# DAC_SPI.net
KiCad netlist of a schematic drawn in Altium Designer
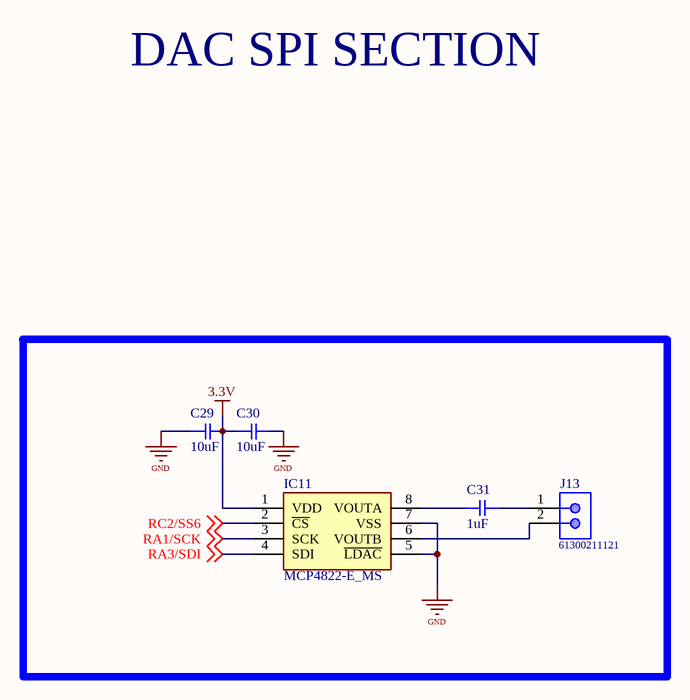
[diagram p0: DAC SPI.SchDoc]

(export (version "E")
  (design (tool "Eeschema 10.0.6"))
  (components
    (comp (ref "C29")
      (value "10uF")
      (footprint "SMD-0805C")
      (description "CAP CER 0.1UF 50V X7R 0805")
      (fields
        (field (name "DIGI-KEY PART NUMBER") "490-11955-1-ND")
        (field (name "PART NUMBER") "GCD21BR71H104KA01L")
      )
      (libsource (lib "capacitor_murata_0805") (part "GCD21BR71H104KA01L"))
    )
    (comp (ref "C30")
      (value "10uF")
      (footprint "SMD-0805C")
      (description "CAP CER 0.1UF 50V X7R 0805")
      (fields
        (field (name "DIGI-KEY PART NUMBER") "490-11955-1-ND")
        (field (name "PART NUMBER") "GCD21BR71H104KA01L")
      )
      (libsource (lib "capacitor_murata_0805") (part "GCD21BR71H104KA01L"))
    )
    (comp (ref "C31")
      (value "1uF")
      (footprint "SMD-0805C")
      (description "CAP CER 0.1UF 50V X7R 0805")
      (fields
        (field (name "DIGI-KEY PART NUMBER") "490-11955-1-ND")
        (field (name "PART NUMBER") "GCD21BR71H104KA01L")
      )
      (libsource (lib "capacitor_murata_0805") (part "GCD21BR71H104KA01L"))
    )
    (comp (ref "IC11")
      (value "MCP4822-E_MS")
      (footprint "SamacSys:SOP65P490X110-8N")
      (description "Integrated Circuit")
      (fields
        (field (name "MANUFACTURER_PART_NUMBER") "MCP4822-E/MS")
        (field (name "MOUSER PART NUMBER") "579-MCP4822-E/MS")
      )
      (libsource (lib "SamacSys") (part "MCP4822-E_MS"))
    )
    (comp (ref "J13")
      (value "61300211121")
      (footprint "61300211121")
      (description "WR-PHD Pin Header, THT, pitch 2.54mm, Single Row, Vertical, 2pin")
      (fields (field (name "PUBLISHER") "Wurth Elektronik"))
      (libsource (lib "SIL_Connectors WR-PHD_rev19a") (part "61300211121"))
    )
  )
  (nets
    (net (code "1") (name "3.3V") (class "Default")
      (node (ref "C29") (pin "2") (pinfunction "2_2") (pintype "passive"))
      (node (ref "C30") (pin "1") (pinfunction "1_1") (pintype "passive"))
      (node (ref "IC11") (pin "1") (pinfunction "VDD_1") (pintype "passive"))
    )
    (net (code "2") (name "GND") (class "Default")
      (node (ref "C29") (pin "1") (pinfunction "1_1") (pintype "passive"))
      (node (ref "C30") (pin "2") (pinfunction "2_2") (pintype "passive"))
      (node (ref "IC11") (pin "5") (pinfunction "~{LDAC}_5") (pintype "passive"))
      (node (ref "IC11") (pin "7") (pinfunction "VSS_7") (pintype "passive"))
    )
    (net (code "3") (name "Net-(C31-Pad1)") (class "Default")
      (node (ref "C31") (pin "1") (pinfunction "1_1") (pintype "passive"))
      (node (ref "J13") (pin "1") (pinfunction "1_1") (pintype "passive"))
    )
    (net (code "4") (name "Net-(IC11-VOUTA)") (class "Default")
      (node (ref "C31") (pin "2") (pinfunction "2_2") (pintype "passive"))
      (node (ref "IC11") (pin "8") (pinfunction "VOUTA_8") (pintype "passive"))
    )
    (net (code "5") (name "Net-(IC11-VOUTB)") (class "Default")
      (node (ref "IC11") (pin "6") (pinfunction "VOUTB_6") (pintype "passive"))
      (node (ref "J13") (pin "2") (pinfunction "2_2") (pintype "passive"))
    )
    (net (code "6") (name "RA1{slash}SCK") (class "Default")
      (node (ref "IC11") (pin "3") (pinfunction "SCK_3") (pintype "passive"))
    )
    (net (code "7") (name "RA3{slash}SDI") (class "Default")
      (node (ref "IC11") (pin "4") (pinfunction "SDI_4") (pintype "passive"))
    )
    (net (code "8") (name "RC2{slash}SS6") (class "Default")
      (node (ref "IC11") (pin "2") (pinfunction "~{CS}_2") (pintype "passive"))
    )
  )
)
